# EEPROM.net
KiCad netlist of a schematic drawn in Altium Designer
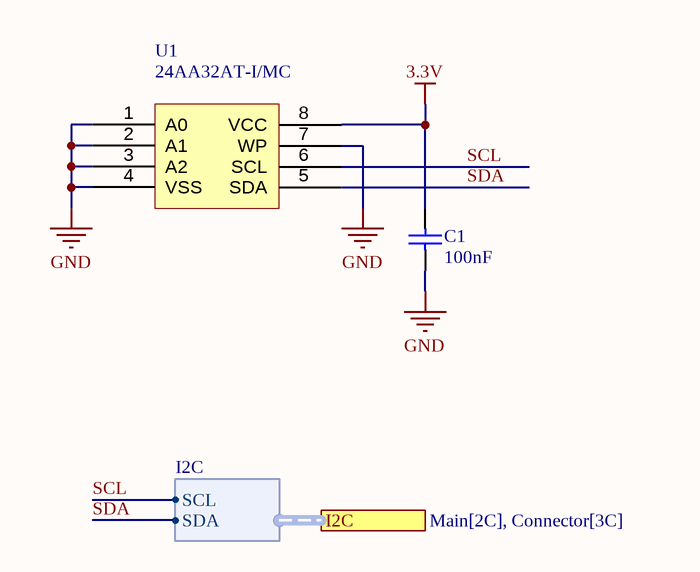
[diagram p0: EEPROM.SchDoc]

(export (version "E")
  (design (tool "Eeschema 10.0.6"))
  (components
    (comp (ref "C1") (value "100nF") (footprint "Capacitor 0201") (libsource (lib "x-io") (part "Capacitor")))
    (comp (ref "U1")
      (value "24AA32AT-I/MC")
      (footprint "TDFN-8 2x3mm")
      (libsource (lib "x-io") (part "24AA32A"))
    )
  )
  (nets
    (net (code "2") (name "/SCL") (class "Default")
      (node (ref "U1") (pin "6") (pinfunction "SCL_6") (pintype "passive"))
    )
    (net (code "3") (name "/SDA") (class "Default")
      (node (ref "U1") (pin "5") (pinfunction "SDA_5") (pintype "passive"))
    )
    (net (code "5") (name "3.3V") (class "Default")
      (node (ref "C1") (pin "2") (pinfunction "2_2") (pintype "passive"))
      (node (ref "U1") (pin "8") (pinfunction "VCC_8") (pintype "passive"))
    )
    (net (code "6") (name "GND") (class "Default")
      (node (ref "C1") (pin "1") (pinfunction "1_1") (pintype "passive"))
      (node (ref "U1") (pin "1") (pinfunction "A0_1") (pintype "passive"))
      (node (ref "U1") (pin "2") (pinfunction "A1_2") (pintype "passive"))
      (node (ref "U1") (pin "3") (pinfunction "A2_3") (pintype "passive"))
      (node (ref "U1") (pin "4") (pinfunction "VSS_4") (pintype "passive"))
      (node (ref "U1") (pin "7") (pinfunction "WP_7") (pintype "passive"))
    )
  )
)
